# ShieldClon_0_00.net
KiCad netlist of a schematic drawn in EAGLE
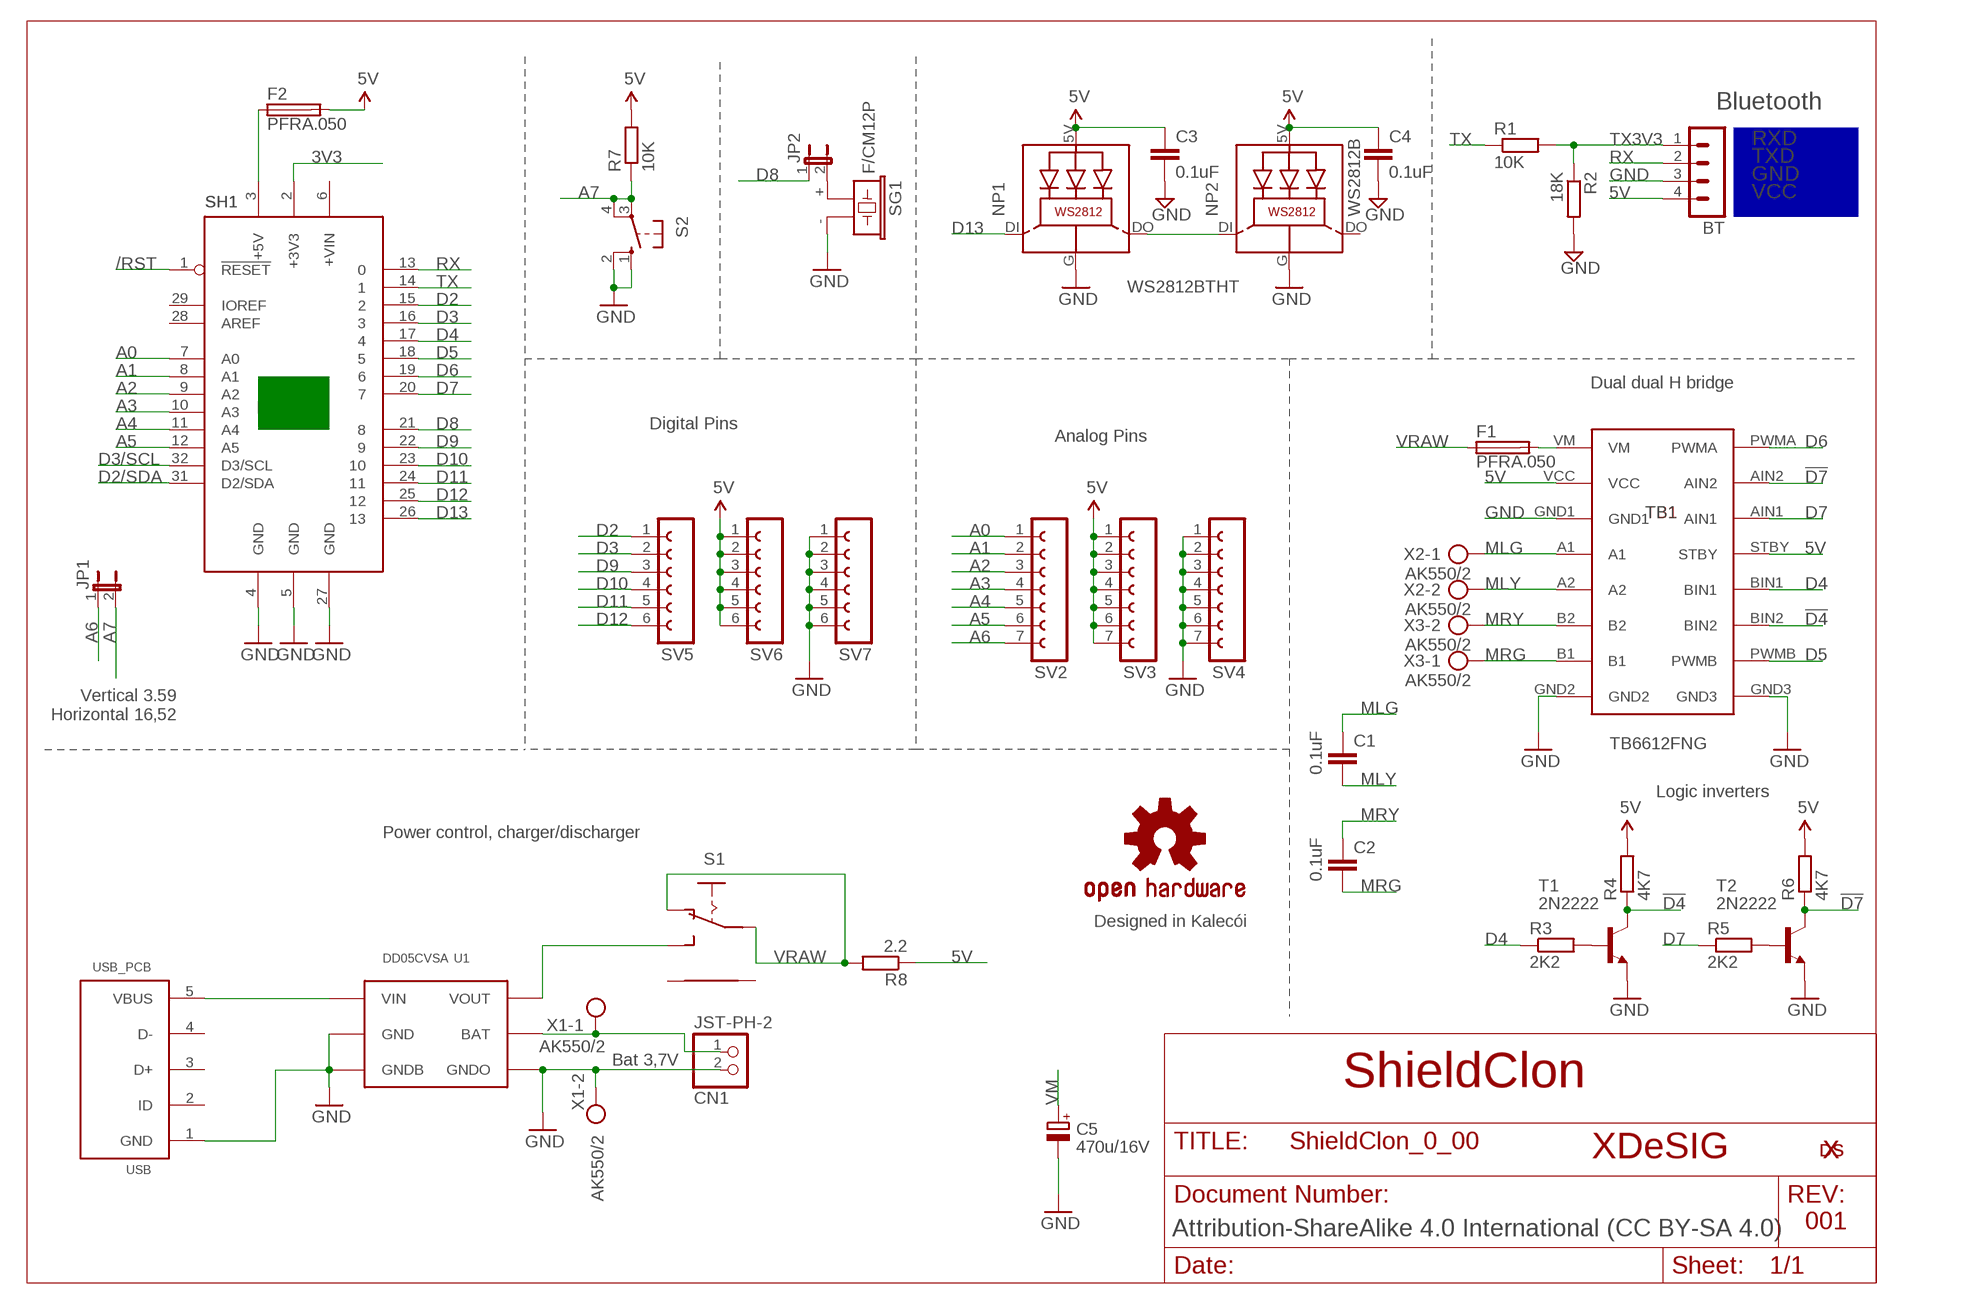
[diagram p0: schematic, sheet 1]

(export (version "E")
  (design (tool "Eeschema 10.0.6"))
  (components
    (comp (ref "BT")
      (value "MA04-1")
      (footprint "eagle-import:MA04-1")
      (libsource (lib "eagle-import") (part "MA04-1"))
    )
    (comp (ref "C1")
      (value "0.1uF")
      (footprint "eagle-import:C050-024X044")
      (libsource (lib "eagle-import") (part "C-EU050-024X044"))
    )
    (comp (ref "C2")
      (value "0.1uF")
      (footprint "eagle-import:C050-024X044")
      (libsource (lib "eagle-import") (part "C-EU050-024X044"))
    )
    (comp (ref "C3")
      (value "0.1uF")
      (footprint "eagle-import:C050-024X044")
      (libsource (lib "eagle-import") (part "C-EU050-024X044"))
    )
    (comp (ref "C4")
      (value "0.1uF")
      (footprint "eagle-import:C050-024X044")
      (libsource (lib "eagle-import") (part "C-EU050-024X044"))
    )
    (comp (ref "C5")
      (value "470u/16V")
      (footprint "eagle-import:E2,5-7")
      (libsource (lib "eagle-import") (part "CPOL-EUE2.5-7"))
    )
    (comp (ref "CN1")
      (value "JST-PH-2")
      (footprint "eagle-import:JST-PH-2-THM-RA")
      (libsource (lib "eagle-import") (part "JST_2PIN-THM-RA"))
    )
    (comp (ref "F1")
      (value "PFRA.050")
      (footprint "eagle-import:TE5")
      (libsource (lib "eagle-import") (part "FUSETE5"))
    )
    (comp (ref "F2")
      (value "PFRA.050")
      (footprint "eagle-import:TE5")
      (libsource (lib "eagle-import") (part "FUSETE5"))
    )
    (comp (ref "JP1")
      (value "JP1E")
      (footprint "eagle-import:JP1")
      (libsource (lib "eagle-import") (part "JP1E"))
    )
    (comp (ref "JP2")
      (value "JUMPER_JP1E")
      (footprint "eagle-import:JUMPER_JP1")
      (libsource (lib "eagle-import") (part "JUMPER_JP1E"))
    )
    (comp (ref "LOGO4")
      (value "OSHW-LOGOS")
      (footprint "eagle-import:OSHW-LOGO-S")
      (libsource (lib "eagle-import") (part "OSHW-LOGOS"))
    )
    (comp (ref "NP1")
      (value "WS2812BTHT")
      (footprint "eagle-import:NEOPIXEL5MM")
      (libsource (lib "eagle-import") (part "WS2812BTHT"))
    )
    (comp (ref "NP2")
      (value "WS2812B")
      (footprint "eagle-import:NEOPIXEL5MM")
      (libsource (lib "eagle-import") (part "WS2812BTHT"))
    )
    (comp (ref "R1")
      (value "10K")
      (footprint "eagle-import:0204_7")
      (libsource (lib "eagle-import") (part "R-EU_0204/7"))
    )
    (comp (ref "R2")
      (value "18K")
      (footprint "eagle-import:0204_7")
      (libsource (lib "eagle-import") (part "R-EU_0204/7"))
    )
    (comp (ref "R3")
      (value "2K2")
      (footprint "eagle-import:0204_7")
      (libsource (lib "eagle-import") (part "R-EU_0204/7"))
    )
    (comp (ref "R4")
      (value "4K7")
      (footprint "eagle-import:0204_7")
      (libsource (lib "eagle-import") (part "R-EU_0204/7"))
    )
    (comp (ref "R5")
      (value "2K2")
      (footprint "eagle-import:0204_7")
      (libsource (lib "eagle-import") (part "R-EU_0204/7"))
    )
    (comp (ref "R6")
      (value "4K7")
      (footprint "eagle-import:0204_7")
      (libsource (lib "eagle-import") (part "R-EU_0204/7"))
    )
    (comp (ref "R7")
      (value "10K")
      (footprint "eagle-import:0204_7")
      (libsource (lib "eagle-import") (part "R-EU_0204/7"))
    )
    (comp (ref "R8")
      (value "2.2")
      (footprint "eagle-import:0204_7")
      (libsource (lib "eagle-import") (part "R-EU_0204/7"))
    )
    (comp (ref "S1")
      (value "ESCORNA_SK12F14D")
      (footprint "eagle-import:ESCORNA_SK-12D07")
      (libsource (lib "eagle-import") (part "ESCORNA_SK12F14D"))
    )
    (comp (ref "S2")
      (value "10-XX")
      (footprint "eagle-import:B3F-10XX")
      (fields (field (name "MPN") "B3F-1000"))
      (libsource (lib "eagle-import") (part "10-XX"))
    )
    (comp (ref "SG1")
      (value "F/CM12P")
      (footprint "eagle-import:F_CM12P")
      (libsource (lib "eagle-import") (part "F/CM12P"))
    )
    (comp (ref "SH1")
      (value "ARDUINO_LEONARDO")
      (footprint "eagle-import:LEONARDO")
      (libsource (lib "eagle-import") (part "ARDUINO_LEONARDO"))
    )
    (comp (ref "SV2")
      (value "FE07-1")
      (footprint "eagle-import:FE07")
      (libsource (lib "eagle-import") (part "FE07-1"))
    )
    (comp (ref "SV3")
      (value "FE07-1")
      (footprint "eagle-import:FE07")
      (libsource (lib "eagle-import") (part "FE07-1"))
    )
    (comp (ref "SV4")
      (value "FE07-1")
      (footprint "eagle-import:FE07")
      (libsource (lib "eagle-import") (part "FE07-1"))
    )
    (comp (ref "SV5")
      (value "FE06-1")
      (footprint "eagle-import:FE06")
      (libsource (lib "eagle-import") (part "FE06-1"))
    )
    (comp (ref "SV6")
      (value "FE06-1")
      (footprint "eagle-import:FE06")
      (libsource (lib "eagle-import") (part "FE06-1"))
    )
    (comp (ref "SV7")
      (value "FE06-1")
      (footprint "eagle-import:FE06")
      (libsource (lib "eagle-import") (part "FE06-1"))
    )
    (comp (ref "T1")
      (value "2N2222")
      (footprint "eagle-import:TO92-EBC-OVAL")
      (libsource (lib "eagle-import") (part "2N2222"))
    )
    (comp (ref "T2")
      (value "2N2222")
      (footprint "eagle-import:TO92-EBC-OVAL")
      (libsource (lib "eagle-import") (part "2N2222"))
    )
    (comp (ref "TB1")
      (value "TB6612FNG")
      (footprint "eagle-import:TB6612FNG")
      (libsource (lib "eagle-import") (part "TB6612FNG"))
    )
    (comp (ref "U$18")
      (value "XDESIG21")
      (footprint "eagle-import:XDESIG")
      (libsource (lib "eagle-import") (part "XDESIG21"))
    )
    (comp (ref "U$19")
      (value "XDESIG5MM")
      (footprint "eagle-import:XDESIG_CU")
      (libsource (lib "eagle-import") (part "XDESIG5MM"))
    )
    (comp (ref "U1")
      (value "DD05CVSA")
      (footprint "eagle-import:DD05CVSA")
      (libsource (lib "eagle-import") (part "DD05CVSA"))
    )
    (comp (ref "USB")
      (value "USB_PCB")
      (footprint "eagle-import:USB_PCB")
      (libsource (lib "eagle-import") (part "USB_PCB"))
    )
    (comp (ref "X1")
      (value "AK550/2")
      (footprint "eagle-import:AK550_2")
      (libsource (lib "eagle-import") (part "AK550/2"))
    )
    (comp (ref "X2")
      (value "AK550/2")
      (footprint "eagle-import:AK550_2")
      (libsource (lib "eagle-import") (part "AK550/2"))
    )
    (comp (ref "X3")
      (value "AK550/2")
      (footprint "eagle-import:AK550_2")
      (libsource (lib "eagle-import") (part "AK550/2"))
    )
  )
  (nets
    (net (code "1") (name "/3V3") (class "Default")
      (node (ref "SH1") (pin "2") (pinfunction "+3V3_2") (pintype "power_in"))
    )
    (net (code "2") (name "/A0") (class "Default")
      (node (ref "SH1") (pin "7") (pinfunction "A0_7") (pintype "bidirectional"))
      (node (ref "SV2") (pin "1") (pinfunction "1_1") (pintype "passive"))
    )
    (net (code "3") (name "/A1") (class "Default")
      (node (ref "SH1") (pin "8") (pinfunction "A1_8") (pintype "bidirectional"))
      (node (ref "SV2") (pin "2") (pinfunction "2_2") (pintype "passive"))
    )
    (net (code "4") (name "/A2") (class "Default")
      (node (ref "SH1") (pin "9") (pinfunction "A2_9") (pintype "bidirectional"))
      (node (ref "SV2") (pin "3") (pinfunction "3_3") (pintype "passive"))
    )
    (net (code "5") (name "/A3") (class "Default")
      (node (ref "SH1") (pin "10") (pinfunction "A3_10") (pintype "bidirectional"))
      (node (ref "SV2") (pin "4") (pinfunction "4_4") (pintype "passive"))
    )
    (net (code "6") (name "/A4") (class "Default")
      (node (ref "SH1") (pin "11") (pinfunction "A4_11") (pintype "bidirectional"))
      (node (ref "SV2") (pin "5") (pinfunction "5_5") (pintype "passive"))
    )
    (net (code "7") (name "/A5") (class "Default")
      (node (ref "SH1") (pin "12") (pinfunction "A5_12") (pintype "bidirectional"))
      (node (ref "SV2") (pin "6") (pinfunction "6_6") (pintype "passive"))
    )
    (net (code "8") (name "/A6") (class "Default")
      (node (ref "JP1") (pin "1") (pinfunction "1_1") (pintype "passive"))
      (node (ref "SV2") (pin "7") (pinfunction "7_7") (pintype "passive"))
    )
    (net (code "9") (name "/A7") (class "Default")
      (node (ref "JP1") (pin "2") (pinfunction "2_2") (pintype "passive"))
      (node (ref "R7") (pin "1") (pinfunction "1_1") (pintype "passive"))
      (node (ref "S2") (pin "3") (pinfunction "P_3") (pintype "passive"))
      (node (ref "S2") (pin "4") (pinfunction "P1_4") (pintype "passive"))
    )
    (net (code "10") (name "/D2") (class "Default")
      (node (ref "SH1") (pin "15") (pinfunction "2_15") (pintype "bidirectional"))
      (node (ref "SV5") (pin "1") (pinfunction "1_1") (pintype "passive"))
    )
    (net (code "11") (name "/D2{slash}SDA") (class "Default")
      (node (ref "SH1") (pin "31") (pinfunction "D2/SDA_31") (pintype "bidirectional"))
    )
    (net (code "12") (name "/D3") (class "Default")
      (node (ref "SH1") (pin "16") (pinfunction "3_16") (pintype "bidirectional"))
      (node (ref "SV5") (pin "2") (pinfunction "2_2") (pintype "passive"))
    )
    (net (code "13") (name "/D3{slash}SCL") (class "Default")
      (node (ref "SH1") (pin "32") (pinfunction "D3/SCL_32") (pintype "bidirectional"))
    )
    (net (code "14") (name "/D4") (class "Default")
      (node (ref "R3") (pin "1") (pinfunction "1_1") (pintype "passive"))
      (node (ref "SH1") (pin "17") (pinfunction "4_17") (pintype "bidirectional"))
      (node (ref "TB1") (pin "BIN1") (pinfunction "BIN1_BIN1") (pintype "bidirectional"))
    )
    (net (code "15") (name "/D5") (class "Default")
      (node (ref "SH1") (pin "18") (pinfunction "5_18") (pintype "bidirectional"))
      (node (ref "TB1") (pin "PWMB") (pinfunction "PWMB_PWMB") (pintype "bidirectional"))
    )
    (net (code "16") (name "/D6") (class "Default")
      (node (ref "SH1") (pin "19") (pinfunction "6_19") (pintype "bidirectional"))
      (node (ref "TB1") (pin "PWMA") (pinfunction "PWMA_PWMA") (pintype "bidirectional"))
    )
    (net (code "17") (name "/D7") (class "Default")
      (node (ref "R5") (pin "1") (pinfunction "1_1") (pintype "passive"))
      (node (ref "SH1") (pin "20") (pinfunction "7_20") (pintype "bidirectional"))
      (node (ref "TB1") (pin "AIN1") (pinfunction "AIN1_AIN1") (pintype "bidirectional"))
    )
    (net (code "18") (name "/D8") (class "Default")
      (node (ref "JP2") (pin "1") (pinfunction "1_1") (pintype "passive"))
      (node (ref "SH1") (pin "21") (pinfunction "8_21") (pintype "bidirectional"))
    )
    (net (code "19") (name "/D9") (class "Default")
      (node (ref "SH1") (pin "22") (pinfunction "9_22") (pintype "bidirectional"))
      (node (ref "SV5") (pin "3") (pinfunction "3_3") (pintype "passive"))
    )
    (net (code "20") (name "/D10") (class "Default")
      (node (ref "SH1") (pin "23") (pinfunction "10_23") (pintype "bidirectional"))
      (node (ref "SV5") (pin "4") (pinfunction "4_4") (pintype "passive"))
    )
    (net (code "21") (name "/D11") (class "Default")
      (node (ref "SH1") (pin "24") (pinfunction "11_24") (pintype "bidirectional"))
      (node (ref "SV5") (pin "5") (pinfunction "5_5") (pintype "passive"))
    )
    (net (code "22") (name "/D12") (class "Default")
      (node (ref "SH1") (pin "25") (pinfunction "12_25") (pintype "bidirectional"))
      (node (ref "SV5") (pin "6") (pinfunction "6_6") (pintype "passive"))
    )
    (net (code "23") (name "/D13") (class "Default")
      (node (ref "NP1") (pin "DI") (pinfunction "DI_DI") (pintype "input"))
      (node (ref "SH1") (pin "26") (pinfunction "13_26") (pintype "bidirectional"))
    )
    (net (code "24") (name "/MLG") (class "Default")
      (node (ref "C1") (pin "1") (pinfunction "1_1") (pintype "passive"))
      (node (ref "TB1") (pin "A1") (pinfunction "A1_A1") (pintype "bidirectional"))
      (node (ref "X2") (pin "1") (pinfunction "KL_1") (pintype "passive"))
    )
    (net (code "25") (name "/MLY") (class "Default")
      (node (ref "C1") (pin "2") (pinfunction "2_2") (pintype "passive"))
      (node (ref "TB1") (pin "A2") (pinfunction "A2_A2") (pintype "bidirectional"))
      (node (ref "X2") (pin "2") (pinfunction "KL_2") (pintype "passive"))
    )
    (net (code "26") (name "/MRG") (class "Default")
      (node (ref "C2") (pin "2") (pinfunction "2_2") (pintype "passive"))
      (node (ref "TB1") (pin "B1") (pinfunction "B1_B1") (pintype "bidirectional"))
      (node (ref "X3") (pin "1") (pinfunction "KL_1") (pintype "passive"))
    )
    (net (code "27") (name "/MRY") (class "Default")
      (node (ref "C2") (pin "1") (pinfunction "1_1") (pintype "passive"))
      (node (ref "TB1") (pin "B2") (pinfunction "B2_B2") (pintype "bidirectional"))
      (node (ref "X3") (pin "2") (pinfunction "KL_2") (pintype "passive"))
    )
    (net (code "28") (name "/RX") (class "Default")
      (node (ref "BT") (pin "2") (pinfunction "2_2") (pintype "passive"))
      (node (ref "SH1") (pin "13") (pinfunction "0_13") (pintype "bidirectional"))
    )
    (net (code "29") (name "/TX") (class "Default")
      (node (ref "R1") (pin "1") (pinfunction "1_1") (pintype "passive"))
      (node (ref "SH1") (pin "14") (pinfunction "1_14") (pintype "bidirectional"))
    )
    (net (code "30") (name "/TX3V3") (class "Default")
      (node (ref "BT") (pin "1") (pinfunction "1_1") (pintype "passive"))
      (node (ref "R1") (pin "2") (pinfunction "2_2") (pintype "passive"))
      (node (ref "R2") (pin "1") (pinfunction "1_1") (pintype "passive"))
    )
    (net (code "31") (name "/VM") (class "Default")
      (node (ref "C5") (pin "+") (pinfunction "+_+") (pintype "passive"))
      (node (ref "F1") (pin "2") (pinfunction "2_2") (pintype "passive"))
      (node (ref "TB1") (pin "VM") (pinfunction "VM_VM") (pintype "bidirectional"))
    )
    (net (code "32") (name "/VRAW") (class "Default")
      (node (ref "F1") (pin "1") (pinfunction "1_1") (pintype "passive"))
      (node (ref "R8") (pin "2") (pinfunction "2_2") (pintype "passive"))
      (node (ref "S1") (pin "P$1") (pinfunction "P_P$1") (pintype "passive"))
      (node (ref "S1") (pin "P$2") (pinfunction "O_P$2") (pintype "passive"))
    )
    (net (code "33") (name "/{slash}RST") (class "Default")
      (node (ref "SH1") (pin "1") (pinfunction "~{RESET}_1") (pintype "bidirectional"))
    )
    (net (code "34") (name "/~{D4}") (class "Default")
      (node (ref "R4") (pin "1") (pinfunction "1_1") (pintype "passive"))
      (node (ref "T1") (pin "C") (pinfunction "C_C") (pintype "passive"))
      (node (ref "TB1") (pin "BIN2") (pinfunction "BIN2_BIN2") (pintype "bidirectional"))
    )
    (net (code "35") (name "/~{D7}") (class "Default")
      (node (ref "R6") (pin "1") (pinfunction "1_1") (pintype "passive"))
      (node (ref "T2") (pin "C") (pinfunction "C_C") (pintype "passive"))
      (node (ref "TB1") (pin "AIN2") (pinfunction "AIN2_AIN2") (pintype "bidirectional"))
    )
    (net (code "36") (name "5V") (class "Default")
      (node (ref "BT") (pin "4") (pinfunction "4_4") (pintype "passive"))
      (node (ref "C3") (pin "1") (pinfunction "1_1") (pintype "passive"))
      (node (ref "C4") (pin "1") (pinfunction "1_1") (pintype "passive"))
      (node (ref "F2") (pin "2") (pinfunction "2_2") (pintype "passive"))
      (node (ref "NP1") (pin "5V") (pinfunction "LEDVDD_5V") (pintype "power_in"))
      (node (ref "NP2") (pin "5V") (pinfunction "LEDVDD_5V") (pintype "power_in"))
      (node (ref "R4") (pin "2") (pinfunction "2_2") (pintype "passive"))
      (node (ref "R6") (pin "2") (pinfunction "2_2") (pintype "passive"))
      (node (ref "R7") (pin "2") (pinfunction "2_2") (pintype "passive"))
      (node (ref "R8") (pin "1") (pinfunction "1_1") (pintype "passive"))
      (node (ref "SV3") (pin "1") (pinfunction "1_1") (pintype "passive"))
      (node (ref "SV3") (pin "2") (pinfunction "2_2") (pintype "passive"))
      (node (ref "SV3") (pin "3") (pinfunction "3_3") (pintype "passive"))
      (node (ref "SV3") (pin "4") (pinfunction "4_4") (pintype "passive"))
      (node (ref "SV3") (pin "5") (pinfunction "5_5") (pintype "passive"))
      (node (ref "SV3") (pin "6") (pinfunction "6_6") (pintype "passive"))
      (node (ref "SV3") (pin "7") (pinfunction "7_7") (pintype "passive"))
      (node (ref "SV6") (pin "1") (pinfunction "1_1") (pintype "passive"))
      (node (ref "SV6") (pin "2") (pinfunction "2_2") (pintype "passive"))
      (node (ref "SV6") (pin "3") (pinfunction "3_3") (pintype "passive"))
      (node (ref "SV6") (pin "4") (pinfunction "4_4") (pintype "passive"))
      (node (ref "SV6") (pin "5") (pinfunction "5_5") (pintype "passive"))
      (node (ref "SV6") (pin "6") (pinfunction "6_6") (pintype "passive"))
      (node (ref "TB1") (pin "STBY") (pinfunction "STBY_STBY") (pintype "bidirectional"))
      (node (ref "TB1") (pin "VCC") (pinfunction "VCC_VCC") (pintype "bidirectional"))
    )
    (net (code "37") (name "GND") (class "Default")
      (node (ref "BT") (pin "3") (pinfunction "3_3") (pintype "passive"))
      (node (ref "C3") (pin "2") (pinfunction "2_2") (pintype "passive"))
      (node (ref "C4") (pin "2") (pinfunction "2_2") (pintype "passive"))
      (node (ref "C5") (pin "-") (pinfunction "-_-") (pintype "passive"))
      (node (ref "CN1") (pin "2") (pinfunction "1_2") (pintype "passive"))
      (node (ref "NP1") (pin "G") (pinfunction "GND_G") (pintype "power_in"))
      (node (ref "NP2") (pin "G") (pinfunction "GND_G") (pintype "power_in"))
      (node (ref "R2") (pin "2") (pinfunction "2_2") (pintype "passive"))
      (node (ref "S2") (pin "1") (pinfunction "S_1") (pintype "passive"))
      (node (ref "S2") (pin "2") (pinfunction "S1_2") (pintype "passive"))
      (node (ref "SG1") (pin "-") (pinfunction "2_-") (pintype "passive"))
      (node (ref "SH1") (pin "27") (pinfunction "GND_27") (pintype "power_in"))
      (node (ref "SH1") (pin "4") (pinfunction "GND_4") (pintype "power_in"))
      (node (ref "SH1") (pin "5") (pinfunction "GND_5") (pintype "power_in"))
      (node (ref "SV4") (pin "1") (pinfunction "1_1") (pintype "passive"))
      (node (ref "SV4") (pin "2") (pinfunction "2_2") (pintype "passive"))
      (node (ref "SV4") (pin "3") (pinfunction "3_3") (pintype "passive"))
      (node (ref "SV4") (pin "4") (pinfunction "4_4") (pintype "passive"))
      (node (ref "SV4") (pin "5") (pinfunction "5_5") (pintype "passive"))
      (node (ref "SV4") (pin "6") (pinfunction "6_6") (pintype "passive"))
      (node (ref "SV4") (pin "7") (pinfunction "7_7") (pintype "passive"))
      (node (ref "SV7") (pin "1") (pinfunction "1_1") (pintype "passive"))
      (node (ref "SV7") (pin "2") (pinfunction "2_2") (pintype "passive"))
      (node (ref "SV7") (pin "3") (pinfunction "3_3") (pintype "passive"))
      (node (ref "SV7") (pin "4") (pinfunction "4_4") (pintype "passive"))
      (node (ref "SV7") (pin "5") (pinfunction "5_5") (pintype "passive"))
      (node (ref "SV7") (pin "6") (pinfunction "6_6") (pintype "passive"))
      (node (ref "T1") (pin "E") (pinfunction "E_E") (pintype "passive"))
      (node (ref "T2") (pin "E") (pinfunction "E_E") (pintype "passive"))
      (node (ref "TB1") (pin "GND1") (pinfunction "GND1_GND1") (pintype "bidirectional"))
      (node (ref "TB1") (pin "GND2") (pinfunction "GND2_GND2") (pintype "bidirectional"))
      (node (ref "TB1") (pin "GND3") (pinfunction "GND3_GND3") (pintype "bidirectional"))
      (node (ref "U1") (pin "P$2") (pinfunction "GND_P$2") (pintype "bidirectional"))
      (node (ref "U1") (pin "P$4") (pinfunction "GNDB_P$4") (pintype "bidirectional"))
      (node (ref "U1") (pin "P$5") (pinfunction "GNDO_P$5") (pintype "bidirectional"))
      (node (ref "USB") (pin "1") (pinfunction "GND_1") (pintype "bidirectional"))
      (node (ref "X1") (pin "2") (pinfunction "KL_2") (pintype "passive"))
    )
    (net (code "38") (name "Net-(CN1-2)") (class "Default")
      (node (ref "CN1") (pin "1") (pinfunction "2_1") (pintype "passive"))
      (node (ref "U1") (pin "P$3") (pinfunction "BAT_P$3") (pintype "bidirectional"))
      (node (ref "X1") (pin "1") (pinfunction "KL_1") (pintype "passive"))
    )
    (net (code "39") (name "Net-(NP1-PadDO)") (class "Default")
      (node (ref "NP1") (pin "DO") (pinfunction "DO_DO") (pintype "output"))
      (node (ref "NP2") (pin "DI") (pinfunction "DI_DI") (pintype "input"))
    )
    (net (code "40") (name "Net-(R3-Pad2)") (class "Default")
      (node (ref "R3") (pin "2") (pinfunction "2_2") (pintype "passive"))
      (node (ref "T1") (pin "B") (pinfunction "B_B") (pintype "passive"))
    )
    (net (code "41") (name "Net-(R5-Pad2)") (class "Default")
      (node (ref "R5") (pin "2") (pinfunction "2_2") (pintype "passive"))
      (node (ref "T2") (pin "B") (pinfunction "B_B") (pintype "passive"))
    )
    (net (code "42") (name "Net-(S1-S)") (class "Default")
      (node (ref "S1") (pin "P$3") (pinfunction "S_P$3") (pintype "passive"))
      (node (ref "U1") (pin "P$6") (pinfunction "VOUT_P$6") (pintype "bidirectional"))
    )
    (net (code "43") (name "Net-(SG1-1)") (class "Default")
      (node (ref "JP2") (pin "2") (pinfunction "2_2") (pintype "passive"))
      (node (ref "SG1") (pin "+") (pinfunction "1_+") (pintype "passive"))
    )
    (net (code "44") (name "Net-(SH1-+5V)") (class "Default")
      (node (ref "F2") (pin "1") (pinfunction "1_1") (pintype "passive"))
      (node (ref "SH1") (pin "3") (pinfunction "+5V_3") (pintype "power_in"))
    )
    (net (code "45") (name "Net-(U1-VIN)") (class "Default")
      (node (ref "U1") (pin "P$1") (pinfunction "VIN_P$1") (pintype "bidirectional"))
      (node (ref "USB") (pin "5") (pinfunction "VBUS_5") (pintype "bidirectional"))
    )
    (net (code "46") (name "unconnected-(NP2-PadDO)") (class "Default")
      (node (ref "NP2") (pin "DO") (pinfunction "DO_DO") (pintype "output"))
    )
    (net (code "47") (name "unconnected-(S1-P$1-PadP$4)") (class "Default")
      (node (ref "S1") (pin "P$4") (pinfunction "P$1_P$4") (pintype "passive"))
    )
    (net (code "48") (name "unconnected-(S1-P$2-PadP$5)") (class "Default")
      (node (ref "S1") (pin "P$5") (pinfunction "P$2_P$5") (pintype "bidirectional"))
    )
    (net (code "49") (name "unconnected-(SH1-+VIN-Pad6)") (class "Default")
      (node (ref "SH1") (pin "6") (pinfunction "+VIN_6") (pintype "bidirectional"))
    )
    (net (code "50") (name "unconnected-(SH1-AREF-Pad28)") (class "Default")
      (node (ref "SH1") (pin "28") (pinfunction "AREF_28") (pintype "bidirectional"))
    )
    (net (code "51") (name "unconnected-(SH1-IOREF-Pad29)") (class "Default")
      (node (ref "SH1") (pin "29") (pinfunction "IOREF_29") (pintype "bidirectional"))
    )
    (net (code "52") (name "unconnected-(USB-D+-Pad3)") (class "Default")
      (node (ref "USB") (pin "3") (pinfunction "D+_3") (pintype "bidirectional"))
    )
    (net (code "53") (name "unconnected-(USB-D--Pad4)") (class "Default")
      (node (ref "USB") (pin "4") (pinfunction "D-_4") (pintype "bidirectional"))
    )
    (net (code "54") (name "unconnected-(USB-ID-Pad2)") (class "Default")
      (node (ref "USB") (pin "2") (pinfunction "ID_2") (pintype "bidirectional"))
    )
  )
)
